# SenseBox-Eye_v1_2.net
KiCad netlist of a schematic drawn in EAGLE
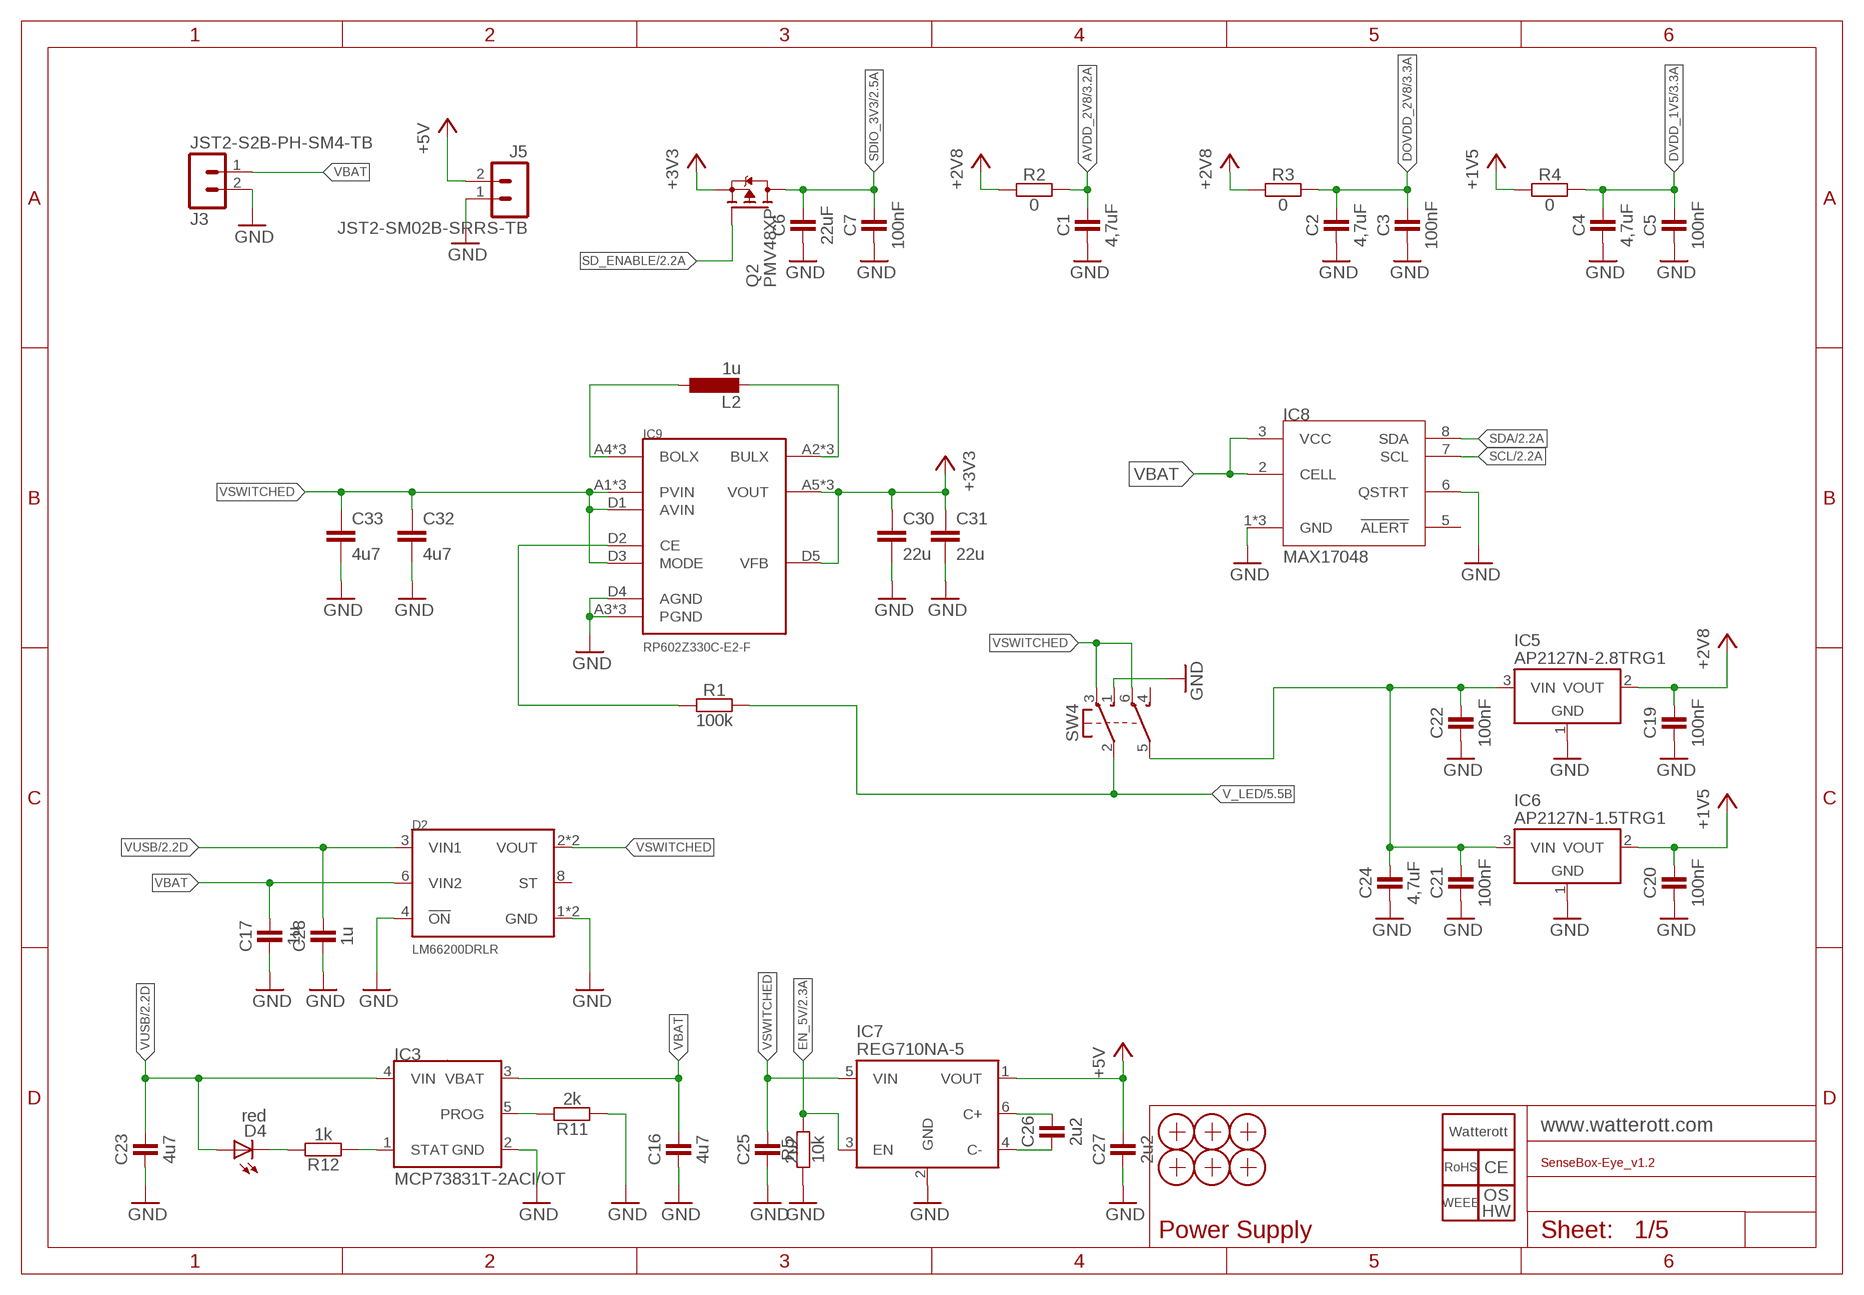
[diagram p0: schematic, sheet 1]
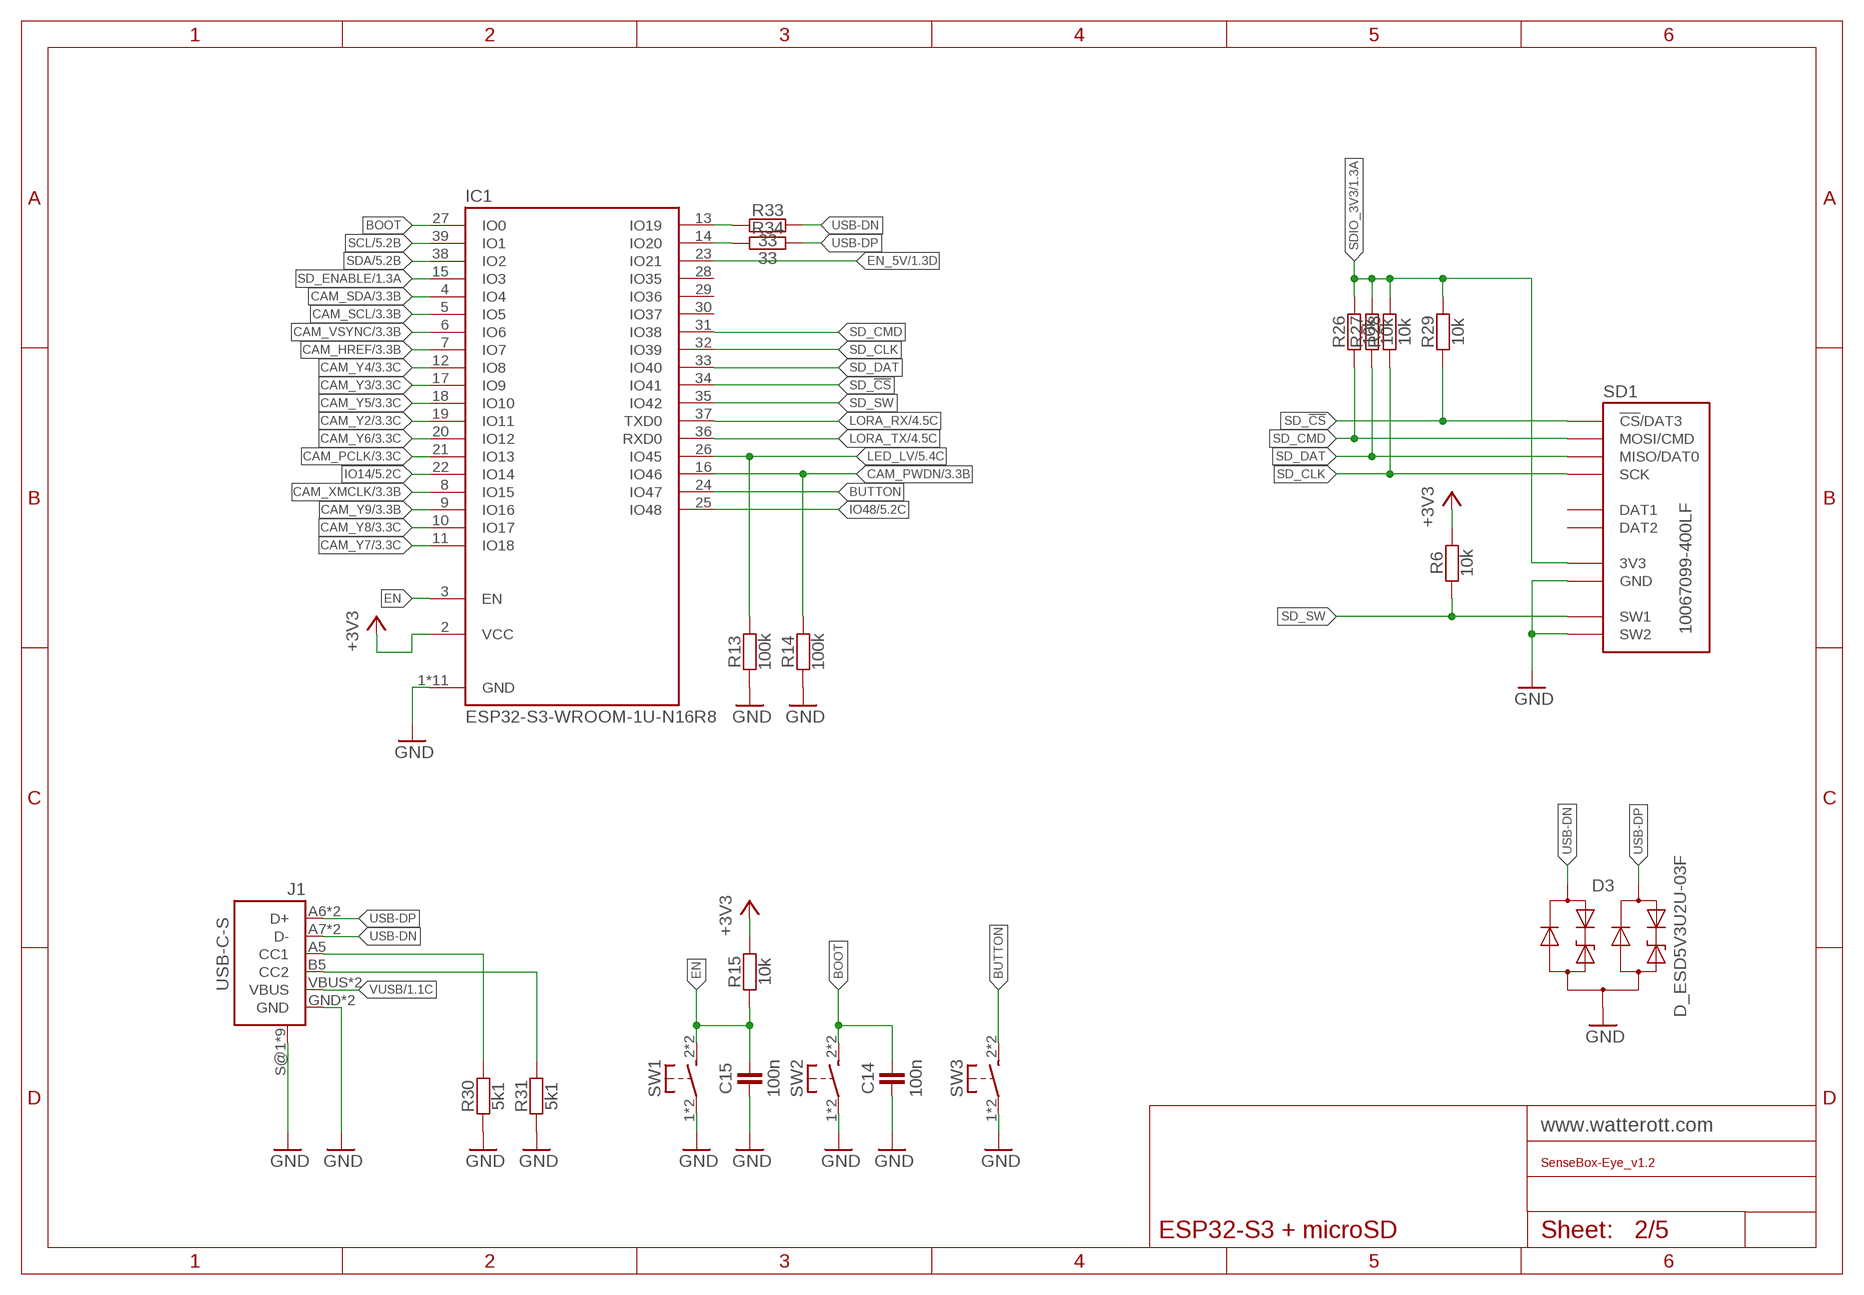
[diagram p1: schematic, sheet 2]
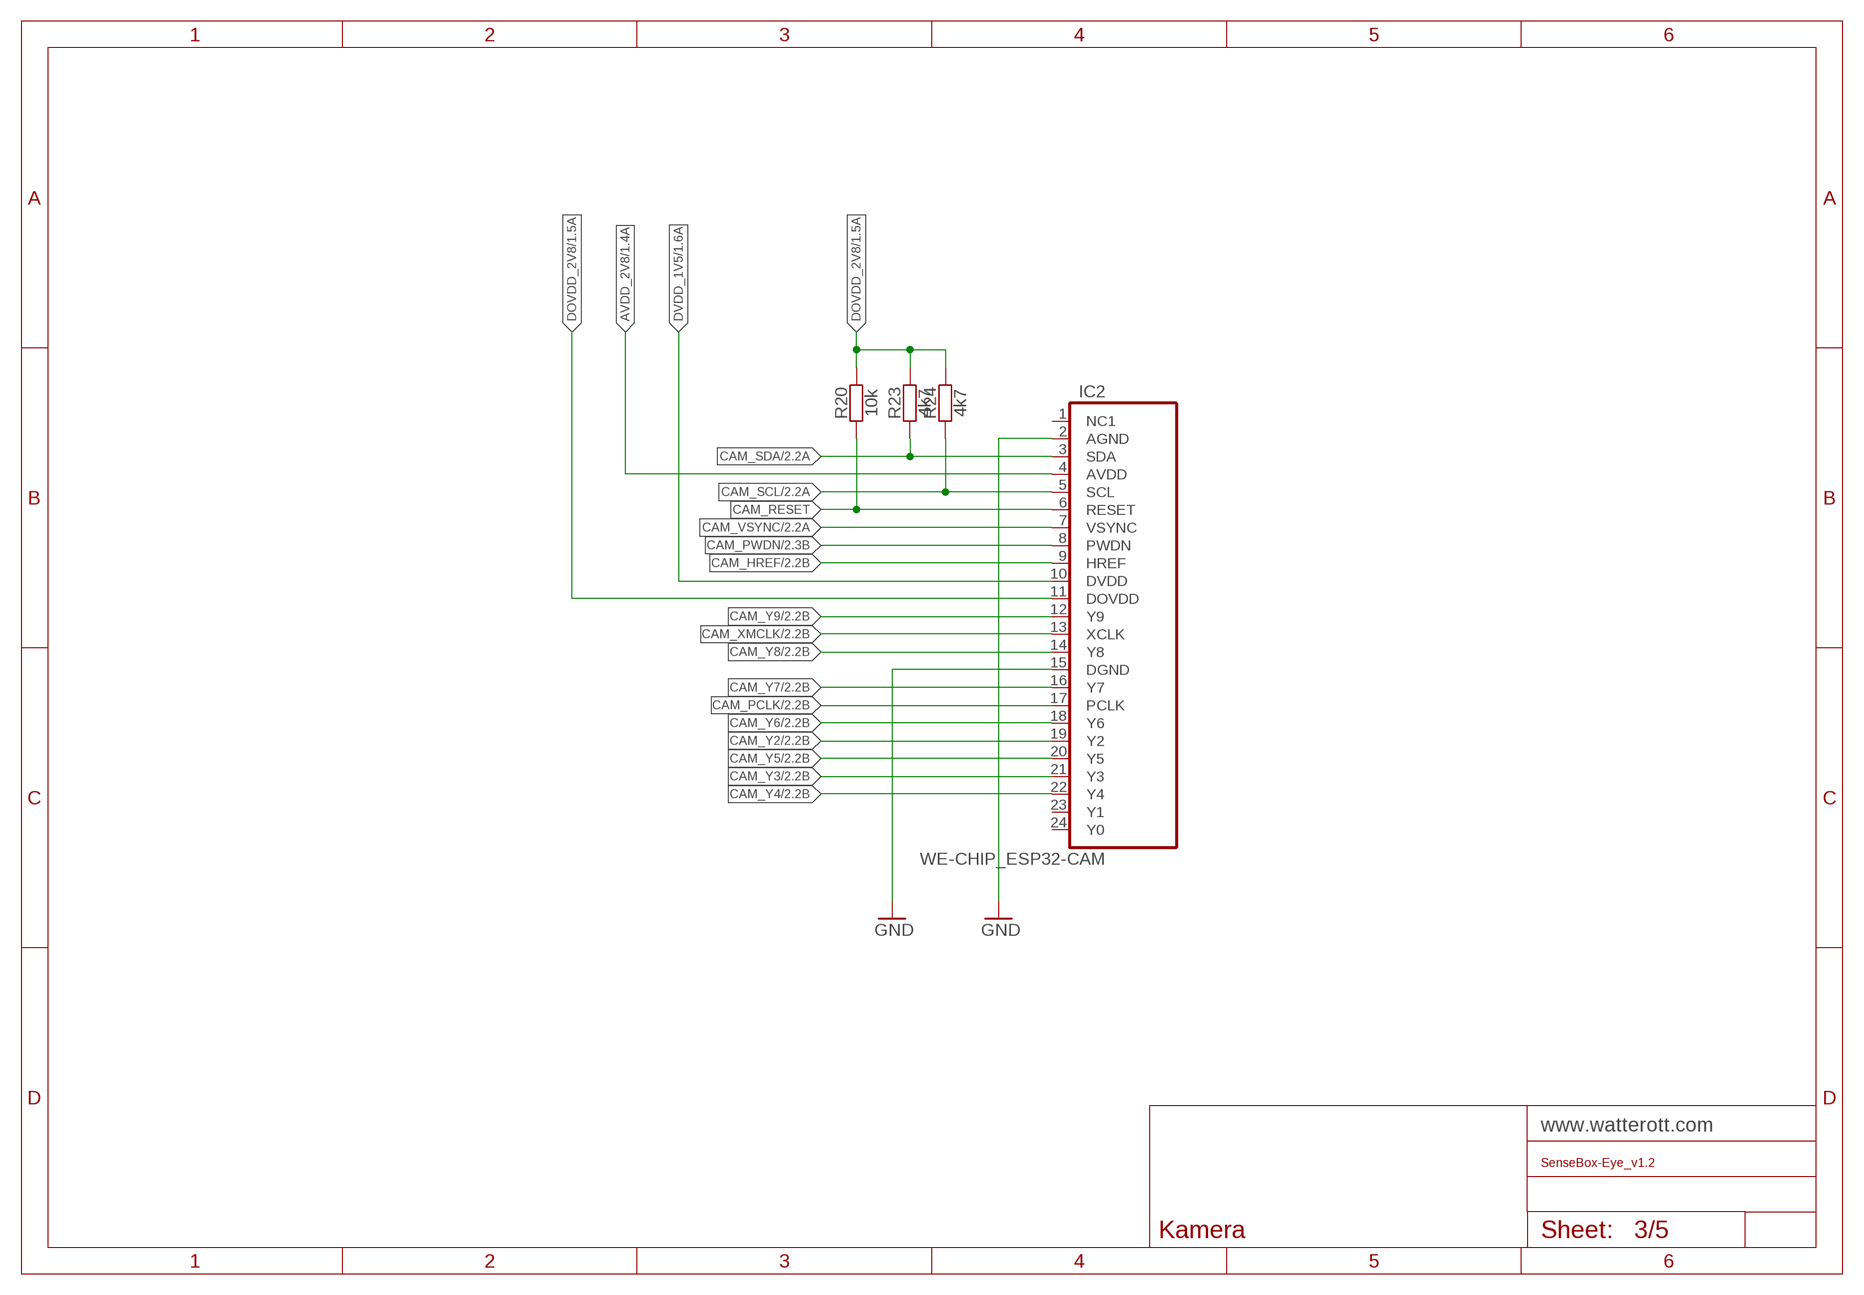
[diagram p2: schematic, sheet 3]
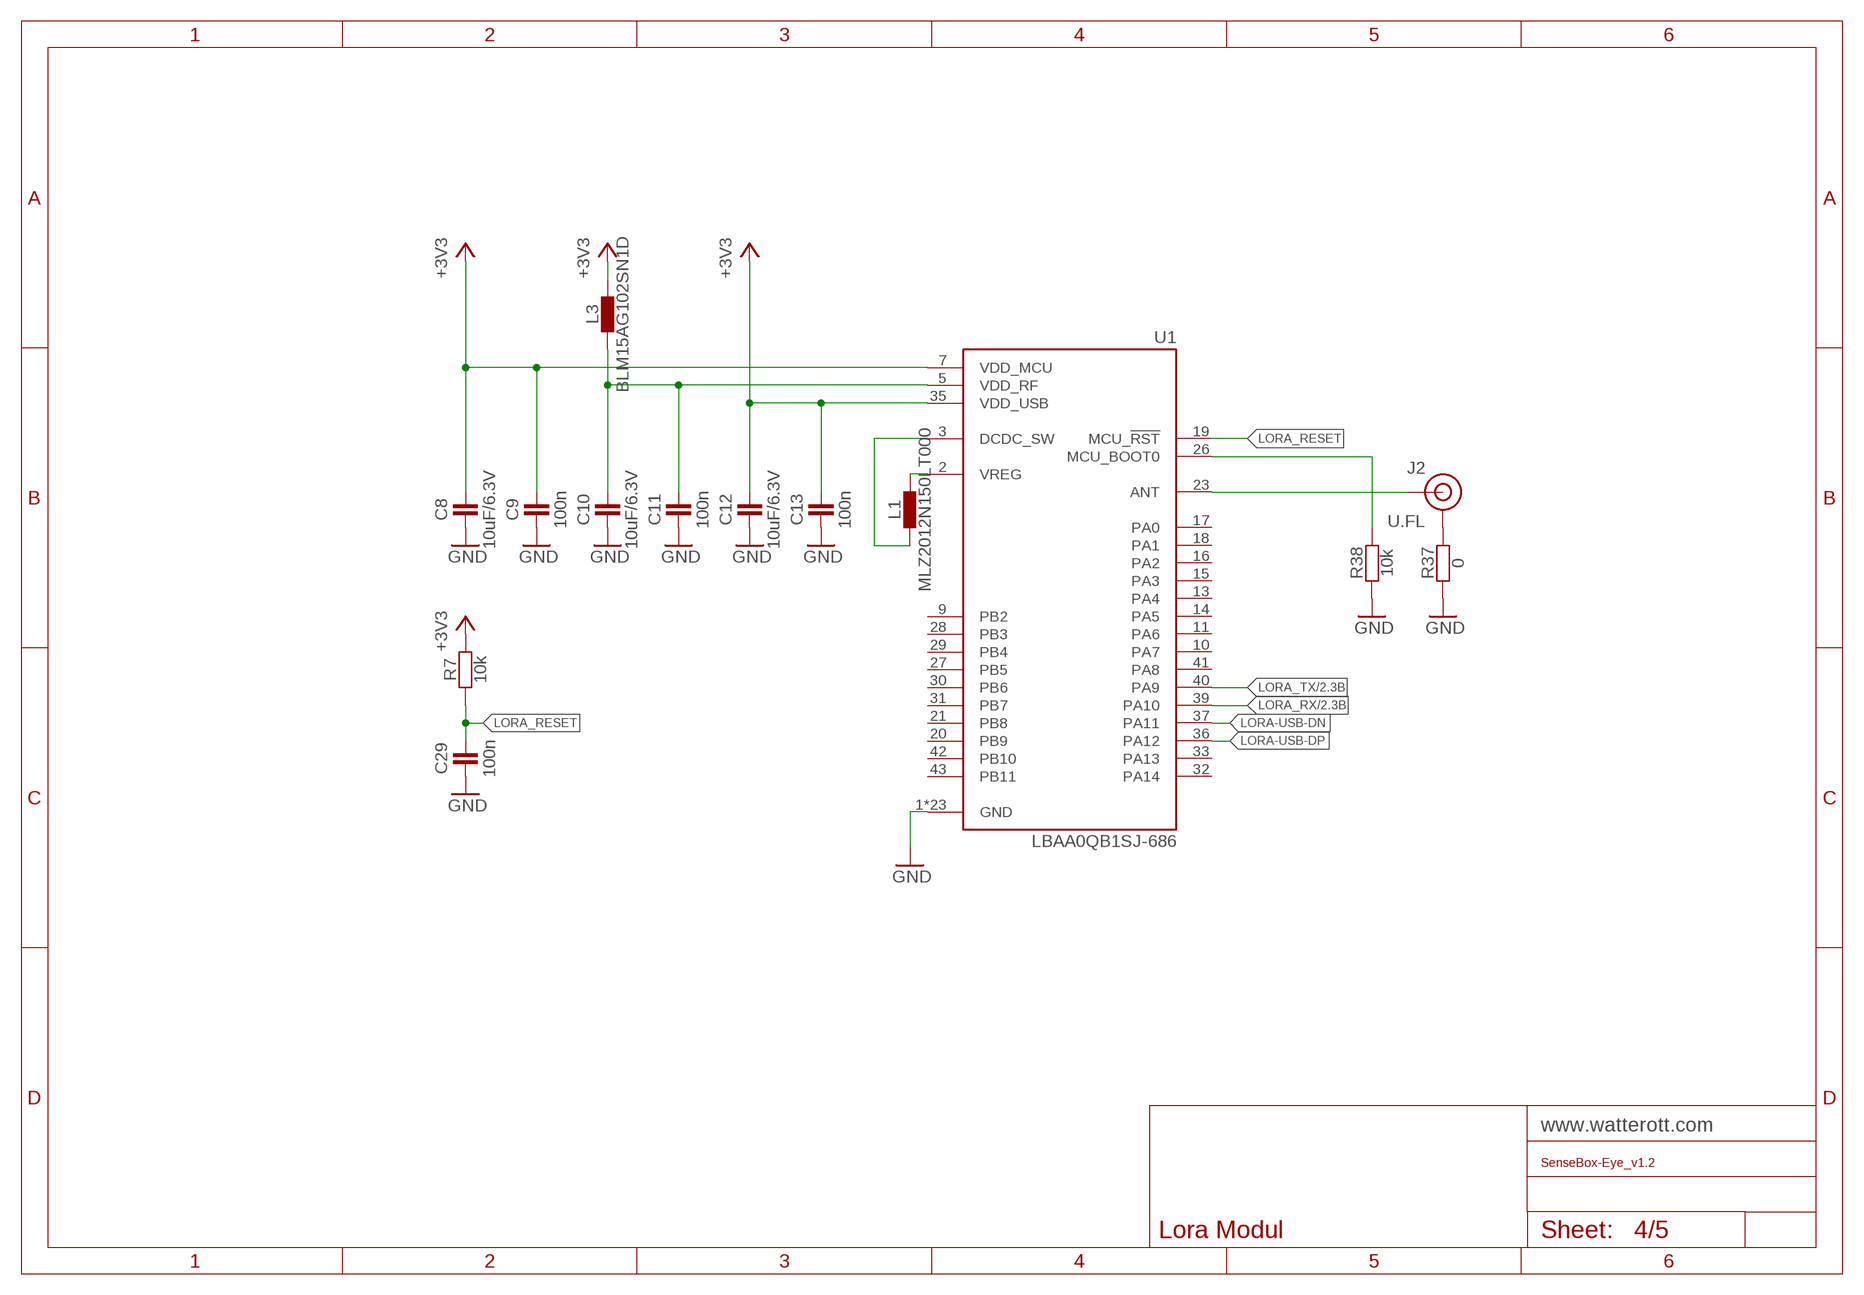
[diagram p3: schematic, sheet 4]
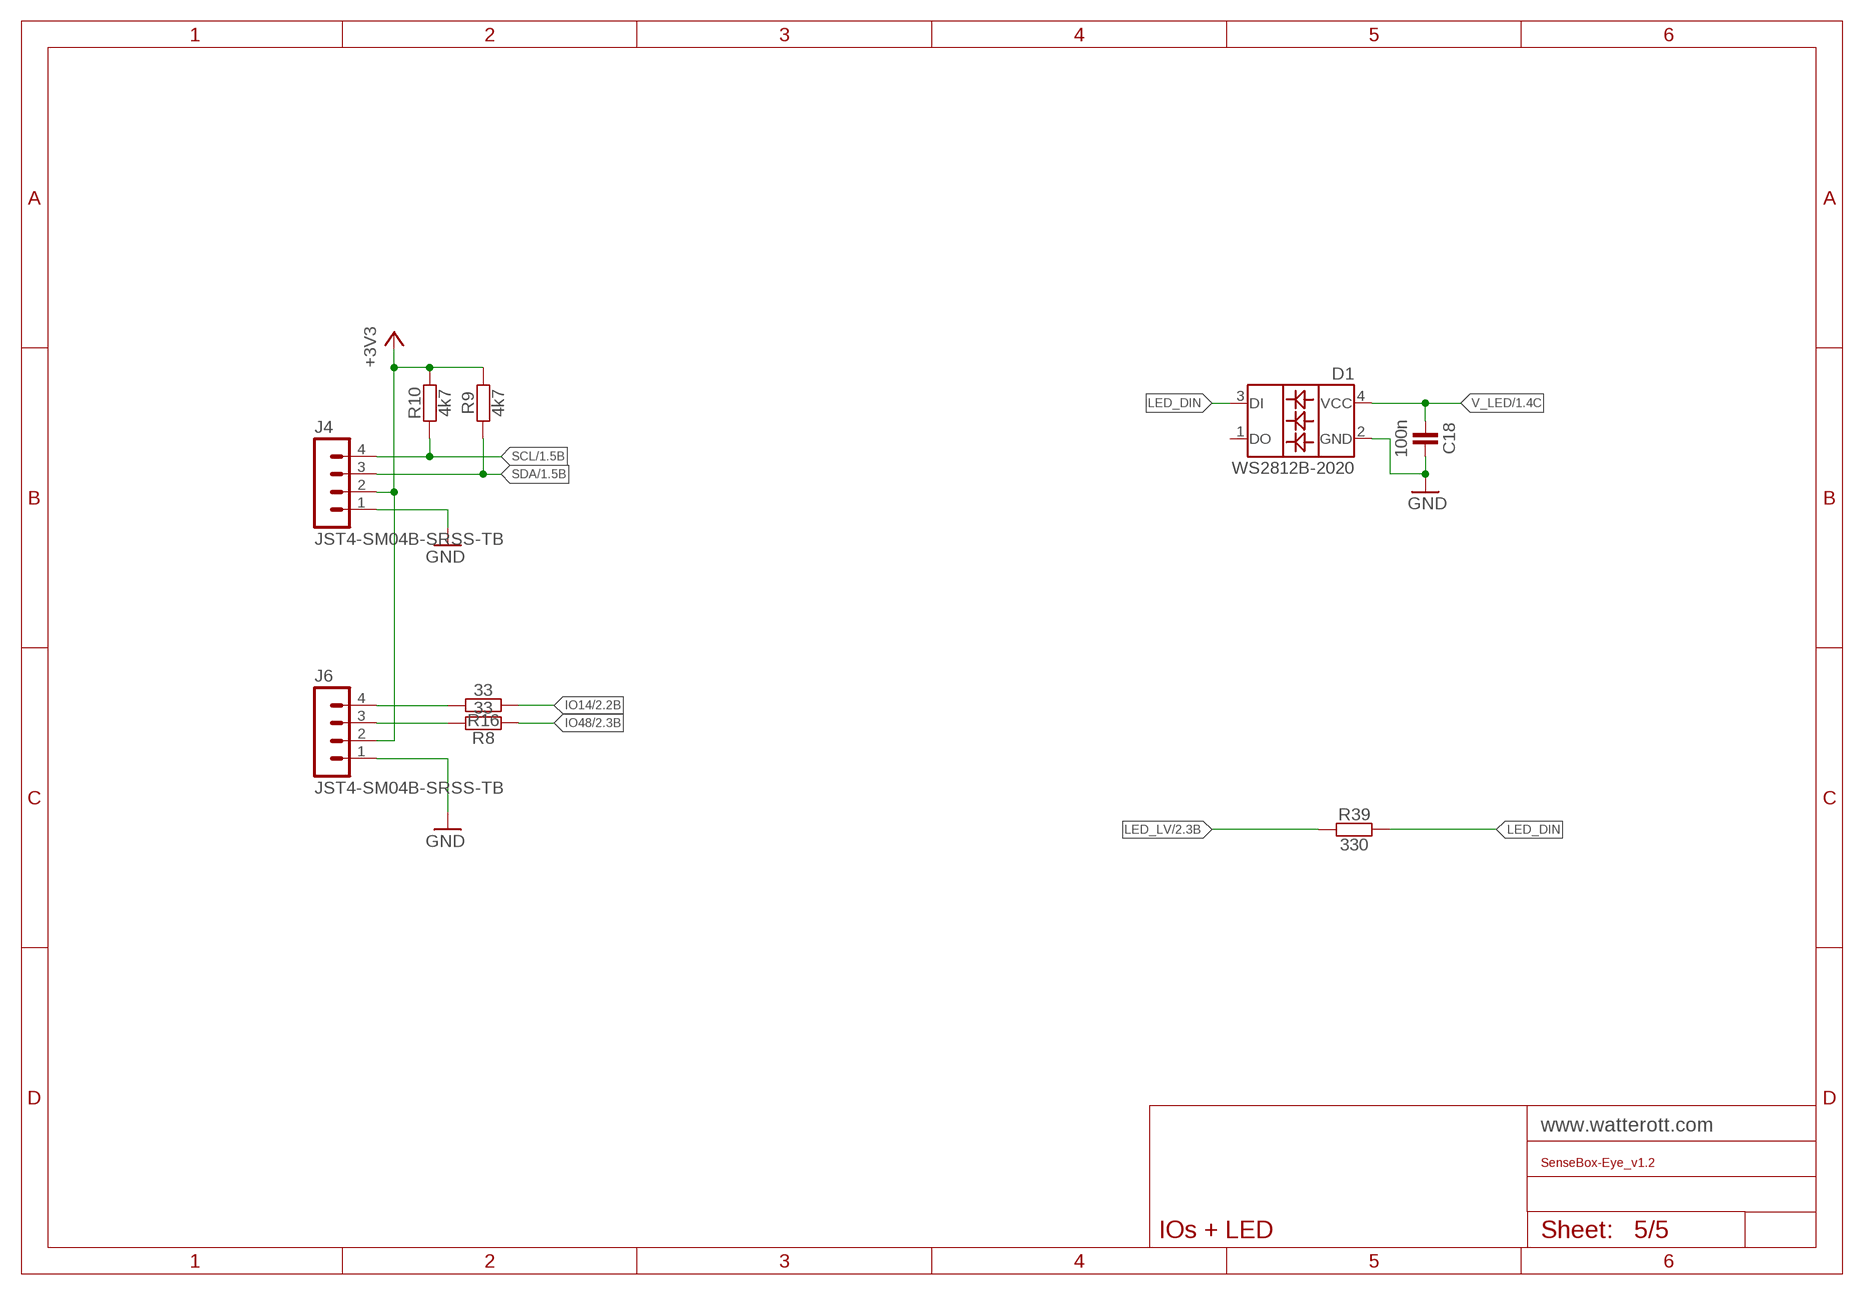
[diagram p4: schematic, sheet 5]

(export (version "E")
  (design (tool "Eeschema 10.0.6"))
  (components
    (comp (ref "C14")
      (value "100n")
      (footprint "eagle-import:C0402")
      (libsource (lib "eagle-import") (part "CAPACITOR-0402"))
    )
    (comp (ref "C15")
      (value "100n")
      (footprint "eagle-import:C0402")
      (libsource (lib "eagle-import") (part "CAPACITOR-0402"))
    )
    (comp (ref "D3")
      (value "D_ESD5V3U2U-03F")
      (footprint "eagle-import:SOT723")
      (libsource (lib "eagle-import") (part "D_ESD5V3U2U-03F"))
    )
    (comp (ref "IC1")
      (value "ESP32-S3-WROOM-1U-N16R8")
      (footprint "eagle-import:ESP32-S3-WROOM-1U")
      (libsource (lib "eagle-import") (part "ESP32_S3-WROOM-1"))
    )
    (comp (ref "J1")
      (value "USB-C-S")
      (footprint "eagle-import:USB-C-S")
      (libsource (lib "eagle-import") (part "USB-C-S"))
    )
    (comp (ref "R6")
      (value "10k")
      (footprint "eagle-import:C0402")
      (libsource (lib "eagle-import") (part "RESISTOR-0402"))
    )
    (comp (ref "R13")
      (value "100k")
      (footprint "eagle-import:C0402")
      (libsource (lib "eagle-import") (part "RESISTOR-0402"))
    )
    (comp (ref "R14")
      (value "100k")
      (footprint "eagle-import:C0402")
      (libsource (lib "eagle-import") (part "RESISTOR-0402"))
    )
    (comp (ref "R15")
      (value "10k")
      (footprint "eagle-import:C0402")
      (libsource (lib "eagle-import") (part "RESISTOR-0402"))
    )
    (comp (ref "R26")
      (value "10k")
      (footprint "eagle-import:C0402")
      (libsource (lib "eagle-import") (part "RESISTOR-0402"))
    )
    (comp (ref "R27")
      (value "10k")
      (footprint "eagle-import:C0402")
      (libsource (lib "eagle-import") (part "RESISTOR-0402"))
    )
    (comp (ref "R28")
      (value "10k")
      (footprint "eagle-import:C0402")
      (libsource (lib "eagle-import") (part "RESISTOR-0402"))
    )
    (comp (ref "R29")
      (value "10k")
      (footprint "eagle-import:C0402")
      (libsource (lib "eagle-import") (part "RESISTOR-0402"))
    )
    (comp (ref "R30")
      (value "5k1")
      (footprint "eagle-import:C0402")
      (libsource (lib "eagle-import") (part "RESISTOR-0402"))
    )
    (comp (ref "R31")
      (value "5k1")
      (footprint "eagle-import:C0402")
      (libsource (lib "eagle-import") (part "RESISTOR-0402"))
    )
    (comp (ref "R33")
      (value "33")
      (footprint "eagle-import:C0402")
      (libsource (lib "eagle-import") (part "RESISTOR-0402"))
    )
    (comp (ref "R34")
      (value "33")
      (footprint "eagle-import:C0402")
      (libsource (lib "eagle-import") (part "RESISTOR-0402"))
    )
    (comp (ref "SD1")
      (value "10067099-400LF")
      (footprint "eagle-import:SD_47309XXXX")
      (libsource (lib "eagle-import") (part "SD-CARD-MSD47"))
    )
    (comp (ref "SW1")
      (value "SW-TACTILE-TL3305")
      (footprint "eagle-import:TL3305")
      (libsource (lib "eagle-import") (part "SW-TACTILE-TL3305"))
    )
    (comp (ref "SW2")
      (value "SW-TACTILE-TL3305")
      (footprint "eagle-import:TL3305")
      (libsource (lib "eagle-import") (part "SW-TACTILE-TL3305"))
    )
    (comp (ref "SW3")
      (value "SW-TACTILE-TL3305")
      (footprint "eagle-import:TL3305")
      (libsource (lib "eagle-import") (part "SW-TACTILE-TL3305"))
    )
    (comp (ref "C8")
      (value "10uF/6.3V")
      (footprint "eagle-import:C0402")
      (libsource (lib "eagle-import") (part "CAPACITOR-0402"))
    )
    (comp (ref "C9")
      (value "100n")
      (footprint "eagle-import:C0402")
      (libsource (lib "eagle-import") (part "CAPACITOR-0402"))
    )
    (comp (ref "C10")
      (value "10uF/6.3V")
      (footprint "eagle-import:C0402")
      (libsource (lib "eagle-import") (part "CAPACITOR-0402"))
    )
    (comp (ref "C11")
      (value "100n")
      (footprint "eagle-import:C0402")
      (libsource (lib "eagle-import") (part "CAPACITOR-0402"))
    )
    (comp (ref "C12")
      (value "10uF/6.3V")
      (footprint "eagle-import:C0402")
      (libsource (lib "eagle-import") (part "CAPACITOR-0402"))
    )
    (comp (ref "C13")
      (value "100n")
      (footprint "eagle-import:C0402")
      (libsource (lib "eagle-import") (part "CAPACITOR-0402"))
    )
    (comp (ref "C29")
      (value "100n")
      (footprint "eagle-import:C0402")
      (libsource (lib "eagle-import") (part "CAPACITOR-0402"))
    )
    (comp (ref "J2")
      (value "U.FL")
      (footprint "eagle-import:U.FL")
      (libsource (lib "eagle-import") (part "U.FL"))
    )
    (comp (ref "L1")
      (value "MLZ2012N150LT000")
      (footprint "eagle-import:C0805")
      (libsource (lib "eagle-import") (part "INDUCTOR-0805"))
    )
    (comp (ref "L3")
      (value "BLM15AG102SN1D")
      (footprint "eagle-import:C0402")
      (libsource (lib "eagle-import") (part "INDUCTOR-0402"))
    )
    (comp (ref "R7")
      (value "10k")
      (footprint "eagle-import:C0402")
      (libsource (lib "eagle-import") (part "RESISTOR-0402"))
    )
    (comp (ref "R37")
      (value "0")
      (footprint "eagle-import:C0402")
      (libsource (lib "eagle-import") (part "RESISTOR-0402"))
    )
    (comp (ref "R38")
      (value "10k")
      (footprint "eagle-import:C0402")
      (libsource (lib "eagle-import") (part "RESISTOR-0402"))
    )
    (comp (ref "U1")
      (value "LBAA0QB1SJ-686")
      (footprint "eagle-import:MODULE_LBAA0QB1SJ-296")
      (fields (field (name "MANUFACTURER") "Murata"))
      (libsource (lib "eagle-import") (part "LBAA0QB1SJ-296"))
    )
    (comp (ref "IC2")
      (value "WE-CHIP_ESP32-CAM")
      (footprint "eagle-import:WE-CHIP_FPC24-0.5-CAM")
      (libsource (lib "eagle-import") (part "WE-CHIP_ESP32-CAM"))
    )
    (comp (ref "R20")
      (value "10k")
      (footprint "eagle-import:C0402")
      (libsource (lib "eagle-import") (part "RESISTOR-0402"))
    )
    (comp (ref "R23")
      (value "4k7")
      (footprint "eagle-import:C0402")
      (libsource (lib "eagle-import") (part "RESISTOR-0402"))
    )
    (comp (ref "R24")
      (value "4k7")
      (footprint "eagle-import:C0402")
      (libsource (lib "eagle-import") (part "RESISTOR-0402"))
    )
    (comp (ref "C18")
      (value "100n")
      (footprint "eagle-import:C0402")
      (libsource (lib "eagle-import") (part "CAPACITOR-0402"))
    )
    (comp (ref "D1")
      (value "WS2812B-2020")
      (footprint "eagle-import:WS2812_2020")
      (libsource (lib "eagle-import") (part "WS2812B-2020"))
    )
    (comp (ref "J4")
      (value "JST4-SM04B-SRSS-TB")
      (footprint "eagle-import:JST_SM04B-SRSS-TB")
      (libsource (lib "eagle-import") (part "JST4-SM04B-SRSS-TB"))
    )
    (comp (ref "J6")
      (value "JST4-SM04B-SRSS-TB")
      (footprint "eagle-import:JST_SM04B-SRSS-TB")
      (libsource (lib "eagle-import") (part "JST4-SM04B-SRSS-TB"))
    )
    (comp (ref "R8")
      (value "33")
      (footprint "eagle-import:C0402")
      (libsource (lib "eagle-import") (part "RESISTOR-0402"))
    )
    (comp (ref "R9")
      (value "4k7")
      (footprint "eagle-import:C0402")
      (libsource (lib "eagle-import") (part "RESISTOR-0402"))
    )
    (comp (ref "R10")
      (value "4k7")
      (footprint "eagle-import:C0402")
      (libsource (lib "eagle-import") (part "RESISTOR-0402"))
    )
    (comp (ref "R16")
      (value "33")
      (footprint "eagle-import:C0402")
      (libsource (lib "eagle-import") (part "RESISTOR-0402"))
    )
    (comp (ref "R39")
      (value "330")
      (footprint "eagle-import:C0402")
      (libsource (lib "eagle-import") (part "RESISTOR-0402"))
    )
    (comp (ref "C1")
      (value "4,7uF")
      (footprint "eagle-import:C0402")
      (libsource (lib "eagle-import") (part "CAPACITOR-0402"))
    )
    (comp (ref "C2")
      (value "4,7uF")
      (footprint "eagle-import:C0402")
      (libsource (lib "eagle-import") (part "CAPACITOR-0402"))
    )
    (comp (ref "C3")
      (value "100nF")
      (footprint "eagle-import:C0402")
      (libsource (lib "eagle-import") (part "CAPACITOR-0402"))
    )
    (comp (ref "C4")
      (value "4,7uF")
      (footprint "eagle-import:C0402")
      (libsource (lib "eagle-import") (part "CAPACITOR-0402"))
    )
    (comp (ref "C5")
      (value "100nF")
      (footprint "eagle-import:C0402")
      (libsource (lib "eagle-import") (part "CAPACITOR-0402"))
    )
    (comp (ref "C6")
      (value "22uF")
      (footprint "eagle-import:C0402")
      (libsource (lib "eagle-import") (part "CAPACITOR-0402"))
    )
    (comp (ref "C7")
      (value "100nF")
      (footprint "eagle-import:C0402")
      (libsource (lib "eagle-import") (part "CAPACITOR-0402"))
    )
    (comp (ref "C16")
      (value "4u7")
      (footprint "eagle-import:C0402")
      (libsource (lib "eagle-import") (part "CAPACITOR-0402"))
    )
    (comp (ref "C17")
      (value "1u")
      (footprint "eagle-import:C0402")
      (libsource (lib "eagle-import") (part "CAPACITOR-0402"))
    )
    (comp (ref "C19")
      (value "100nF")
      (footprint "eagle-import:C0402")
      (libsource (lib "eagle-import") (part "CAPACITOR-0402"))
    )
    (comp (ref "C20")
      (value "100nF")
      (footprint "eagle-import:C0402")
      (libsource (lib "eagle-import") (part "CAPACITOR-0402"))
    )
    (comp (ref "C21")
      (value "100nF")
      (footprint "eagle-import:C0402")
      (libsource (lib "eagle-import") (part "CAPACITOR-0402"))
    )
    (comp (ref "C22")
      (value "100nF")
      (footprint "eagle-import:C0402")
      (libsource (lib "eagle-import") (part "CAPACITOR-0402"))
    )
    (comp (ref "C23")
      (value "4u7")
      (footprint "eagle-import:C0402")
      (libsource (lib "eagle-import") (part "CAPACITOR-0402"))
    )
    (comp (ref "C24")
      (value "4,7uF")
      (footprint "eagle-import:C0402")
      (libsource (lib "eagle-import") (part "CAPACITOR-0402"))
    )
    (comp (ref "C25")
      (value "2u2")
      (footprint "eagle-import:C0402")
      (libsource (lib "eagle-import") (part "CAPACITOR-0402"))
    )
    (comp (ref "C26")
      (value "2u2")
      (footprint "eagle-import:C0402")
      (libsource (lib "eagle-import") (part "CAPACITOR-0402"))
    )
    (comp (ref "C27")
      (value "2u2")
      (footprint "eagle-import:C0402")
      (libsource (lib "eagle-import") (part "CAPACITOR-0402"))
    )
    (comp (ref "C28")
      (value "1u")
      (footprint "eagle-import:C0402")
      (libsource (lib "eagle-import") (part "CAPACITOR-0402"))
    )
    (comp (ref "C30")
      (value "22u")
      (footprint "eagle-import:0805N")
      (fields (field (name "VOLTAGE") "6V3"))
      (libsource (lib "eagle-import") (part "C_0805N_22U"))
    )
    (comp (ref "C31")
      (value "22u")
      (footprint "eagle-import:0805N")
      (fields (field (name "VOLTAGE") "6V3"))
      (libsource (lib "eagle-import") (part "C_0805N_22U"))
    )
    (comp (ref "C32")
      (value "4u7")
      (footprint "eagle-import:0603N")
      (fields (field (name "VOLTAGE") "6V3"))
      (libsource (lib "eagle-import") (part "C_0603N_4U7"))
    )
    (comp (ref "C33")
      (value "4u7")
      (footprint "eagle-import:0603N")
      (fields (field (name "VOLTAGE") "6V3"))
      (libsource (lib "eagle-import") (part "C_0603N_4U7"))
    )
    (comp (ref "D2")
      (value "LM66200DRLR")
      (footprint "eagle-import:SOT-5X3")
      (libsource (lib "eagle-import") (part "LM66200"))
    )
    (comp (ref "D4")
      (value "red")
      (footprint "eagle-import:0603N")
      (libsource (lib "eagle-import") (part "LED_0603N_RED"))
    )
    (comp (ref "IC3")
      (value "MCP73831T-2ACI/OT")
      (footprint "eagle-import:SOT23-5")
      (libsource (lib "eagle-import") (part "MCP73831_SOT23-5_MCP73831T-2ACI/OT"))
    )
    (comp (ref "IC5")
      (value "AP2127N-2.8TRG1")
      (footprint "eagle-import:SOT23")
      (libsource (lib "eagle-import") (part "VREG-TS9011-3V3"))
    )
    (comp (ref "IC6")
      (value "AP2127N-1.5TRG1")
      (footprint "eagle-import:SOT23")
      (libsource (lib "eagle-import") (part "VREG-TS9011-3V3"))
    )
    (comp (ref "IC7")
      (value "REG710NA-5")
      (footprint "eagle-import:SOT23-6")
      (libsource (lib "eagle-import") (part "REG710NA-5"))
    )
    (comp (ref "IC8")
      (value "MAX17048")
      (footprint "eagle-import:UDFN8_2020")
      (libsource (lib "eagle-import") (part "MAX1704X"))
    )
    (comp (ref "IC9")
      (value "RP602Z330C-E2-F")
      (footprint "eagle-import:WLCSP-20-P1")
      (libsource (lib "eagle-import") (part "RP602_WLCSP-20-P1_RP602Z330C-E2-F"))
    )
    (comp (ref "J3")
      (value "JST2-S2B-PH-SM4-TB")
      (footprint "eagle-import:JST_S2B-PH-SM4-TB")
      (libsource (lib "eagle-import") (part "JST2-S2B-PH-SM4-TB"))
    )
    (comp (ref "J5")
      (value "JST2-SM02B-SRRS-TB")
      (footprint "eagle-import:JST_SM02B-SRSS-TB")
      (libsource (lib "eagle-import") (part "JST2-SM02B-SRRS-TB"))
    )
    (comp (ref "L2")
      (value "1u")
      (footprint "eagle-import:5040")
      (libsource (lib "eagle-import") (part "L_5040_WE-LQS-1U"))
    )
    (comp (ref "LOGO2")
      (value "LOGO_CE-2")
      (footprint "eagle-import:CE_2MM")
      (libsource (lib "eagle-import") (part "LOGO_CE-2"))
    )
    (comp (ref "LOGO3")
      (value "LOGO_OSHW-2")
      (footprint "eagle-import:OSHW_2MM")
      (libsource (lib "eagle-import") (part "LOGO_OSHW-2"))
    )
    (comp (ref "LOGO4")
      (value "LOGO_ROHS-2")
      (footprint "eagle-import:ROHS_2MM")
      (libsource (lib "eagle-import") (part "LOGO_ROHS-2"))
    )
    (comp (ref "LOGO5")
      (value "LOGO_WEEE-4")
      (footprint "eagle-import:WEEE_4MM")
      (libsource (lib "eagle-import") (part "LOGO_WEEE-4"))
    )
    (comp (ref "LOGO6")
      (value "LOGO_SPARK-2")
      (footprint "eagle-import:SPARK_2MM")
      (libsource (lib "eagle-import") (part "LOGO_SPARK-2"))
    )
    (comp (ref "Q2")
      (value "PMV48XP")
      (footprint "eagle-import:SOT23")
      (fields (field (name "VOLTAGE") "20"))
      (libsource (lib "eagle-import") (part "MOSFET-P_SOT23'_PMV48XP"))
    )
    (comp (ref "R1")
      (value "100k")
      (footprint "eagle-import:C0402")
      (libsource (lib "eagle-import") (part "RESISTOR-0402"))
    )
    (comp (ref "R2")
      (value "0")
      (footprint "eagle-import:C0402")
      (libsource (lib "eagle-import") (part "RESISTOR-0402"))
    )
    (comp (ref "R3")
      (value "0")
      (footprint "eagle-import:C0402")
      (libsource (lib "eagle-import") (part "RESISTOR-0402"))
    )
    (comp (ref "R4")
      (value "0")
      (footprint "eagle-import:C0402")
      (libsource (lib "eagle-import") (part "RESISTOR-0402"))
    )
    (comp (ref "R5")
      (value "10k")
      (footprint "eagle-import:C0402")
      (libsource (lib "eagle-import") (part "RESISTOR-0402"))
    )
    (comp (ref "R11")
      (value "2k")
      (footprint "eagle-import:C0402")
      (libsource (lib "eagle-import") (part "RESISTOR-0402"))
    )
    (comp (ref "R12")
      (value "1k")
      (footprint "eagle-import:C0402")
      (libsource (lib "eagle-import") (part "RESISTOR-0402"))
    )
    (comp (ref "SW4")
      (value "SW-2UM-CUS22B")
      (footprint "eagle-import:CUS22B")
      (libsource (lib "eagle-import") (part "SW-2UM-CUS22B"))
    )
    (comp (ref "X1")
      (value "PASSER-04")
      (footprint "eagle-import:PASSER_04MM")
      (libsource (lib "eagle-import") (part "PASSER-04"))
    )
    (comp (ref "X2")
      (value "PASSER-04")
      (footprint "eagle-import:PASSER_04MM")
      (libsource (lib "eagle-import") (part "PASSER-04"))
    )
    (comp (ref "X3")
      (value "PASSER-04")
      (footprint "eagle-import:PASSER_04MM")
      (libsource (lib "eagle-import") (part "PASSER-04"))
    )
    (comp (ref "X4")
      (value "PASSER-04")
      (footprint "eagle-import:PASSER_04MM")
      (libsource (lib "eagle-import") (part "PASSER-04"))
    )
    (comp (ref "X5")
      (value "PASSER-04")
      (footprint "eagle-import:PASSER_04MM")
      (libsource (lib "eagle-import") (part "PASSER-04"))
    )
    (comp (ref "X6")
      (value "PASSER-04")
      (footprint "eagle-import:PASSER_04MM")
      (libsource (lib "eagle-import") (part "PASSER-04"))
    )
  )
  (nets
    (net (code "1") (name "+1V5") (class "Default")
      (node (ref "C20") (pin "2") (pinfunction "2_2") (pintype "passive"))
      (node (ref "IC6") (pin "2") (pinfunction "VOUT_2") (pintype "power_in"))
      (node (ref "R4") (pin "1") (pinfunction "1_1") (pintype "passive"))
    )
    (net (code "2") (name "+2V8") (class "Default")
      (node (ref "C19") (pin "2") (pinfunction "2_2") (pintype "passive"))
      (node (ref "IC5") (pin "2") (pinfunction "VOUT_2") (pintype "power_in"))
      (node (ref "R2") (pin "1") (pinfunction "1_1") (pintype "passive"))
      (node (ref "R3") (pin "1") (pinfunction "1_1") (pintype "passive"))
    )
    (net (code "3") (name "+3V3") (class "Default")
      (node (ref "C12") (pin "2") (pinfunction "2_2") (pintype "passive"))
      (node (ref "C13") (pin "2") (pinfunction "2_2") (pintype "passive"))
      (node (ref "C30") (pin "1") (pinfunction "1_1") (pintype "passive"))
      (node (ref "C31") (pin "1") (pinfunction "1_1") (pintype "passive"))
      (node (ref "C8") (pin "2") (pinfunction "2_2") (pintype "passive"))
      (node (ref "C9") (pin "2") (pinfunction "2_2") (pintype "passive"))
      (node (ref "IC1") (pin "2") (pinfunction "VCC_2") (pintype "power_in"))
      (node (ref "IC9") (pin "A5") (pinfunction "VOUT_A5") (pintype "power_in"))
      (node (ref "IC9") (pin "B5") (pinfunction "VOUT_B5") (pintype "power_in"))
      (node (ref "IC9") (pin "C5") (pinfunction "VOUT_C5") (pintype "power_in"))
      (node (ref "IC9") (pin "D5") (pinfunction "VFB_D5") (pintype "input"))
      (node (ref "J4") (pin "2") (pinfunction "2_2") (pintype "passive"))
      (node (ref "J6") (pin "2") (pinfunction "2_2") (pintype "passive"))
      (node (ref "L3") (pin "2") (pinfunction "2_2") (pintype "passive"))
      (node (ref "Q2") (pin "2") (pinfunction "S_2") (pintype "passive"))
      (node (ref "R10") (pin "1") (pinfunction "1_1") (pintype "passive"))
      (node (ref "R15") (pin "2") (pinfunction "2_2") (pintype "passive"))
      (node (ref "R6") (pin "2") (pinfunction "2_2") (pintype "passive"))
      (node (ref "R7") (pin "2") (pinfunction "2_2") (pintype "passive"))
      (node (ref "R9") (pin "1") (pinfunction "1_1") (pintype "passive"))
      (node (ref "U1") (pin "35") (pinfunction "VDD_USB_35") (pintype "power_in"))
      (node (ref "U1") (pin "7") (pinfunction "VDD_MCU_7") (pintype "power_in"))
    )
    (net (code "4") (name "+5V") (class "Default")
      (node (ref "C27") (pin "2") (pinfunction "2_2") (pintype "passive"))
      (node (ref "IC7") (pin "1") (pinfunction "VOUT_1") (pintype "power_in"))
      (node (ref "J5") (pin "2") (pinfunction "2_2") (pintype "passive"))
    )
    (net (code "5") (name "AVDD_2V8") (class "Default")
      (node (ref "C1") (pin "2") (pinfunction "2_2") (pintype "passive"))
      (node (ref "IC2") (pin "4") (pinfunction "AVDD_4") (pintype "bidirectional"))
      (node (ref "R2") (pin "2") (pinfunction "2_2") (pintype "passive"))
    )
    (net (code "6") (name "BOOT") (class "Default")
      (node (ref "C14") (pin "2") (pinfunction "2_2") (pintype "passive"))
      (node (ref "IC1") (pin "27") (pinfunction "IO0_27") (pintype "bidirectional"))
      (node (ref "SW2") (pin "2") (pinfunction "S1_2") (pintype "passive"))
      (node (ref "SW2") (pin "3") (pinfunction "S1_3") (pintype "passive"))
    )
    (net (code "7") (name "BUTTON") (class "Default")
      (node (ref "IC1") (pin "24") (pinfunction "IO47_24") (pintype "bidirectional"))
      (node (ref "SW3") (pin "2") (pinfunction "S1_2") (pintype "passive"))
      (node (ref "SW3") (pin "3") (pinfunction "S1_3") (pintype "passive"))
    )
    (net (code "8") (name "CAM_HREF") (class "Default")
      (node (ref "IC1") (pin "7") (pinfunction "IO7_7") (pintype "bidirectional"))
      (node (ref "IC2") (pin "9") (pinfunction "HREF_9") (pintype "bidirectional"))
    )
    (net (code "9") (name "CAM_PCLK") (class "Default")
      (node (ref "IC1") (pin "21") (pinfunction "IO13_21") (pintype "bidirectional"))
      (node (ref "IC2") (pin "17") (pinfunction "PCLK_17") (pintype "bidirectional"))
    )
    (net (code "10") (name "CAM_PWDN") (class "Default")
      (node (ref "IC1") (pin "16") (pinfunction "IO46_16") (pintype "bidirectional"))
      (node (ref "IC2") (pin "8") (pinfunction "PWDN_8") (pintype "bidirectional"))
      (node (ref "R14") (pin "2") (pinfunction "2_2") (pintype "passive"))
    )
    (net (code "11") (name "CAM_RESET") (class "Default")
      (node (ref "IC2") (pin "6") (pinfunction "RESET_6") (pintype "bidirectional"))
      (node (ref "R20") (pin "1") (pinfunction "1_1") (pintype "passive"))
    )
    (net (code "12") (name "CAM_SCL") (class "Default")
      (node (ref "IC1") (pin "5") (pinfunction "IO5_5") (pintype "bidirectional"))
      (node (ref "IC2") (pin "5") (pinfunction "SCL_5") (pintype "bidirectional"))
      (node (ref "R24") (pin "1") (pinfunction "1_1") (pintype "passive"))
    )
    (net (code "13") (name "CAM_SDA") (class "Default")
      (node (ref "IC1") (pin "4") (pinfunction "IO4_4") (pintype "bidirectional"))
      (node (ref "IC2") (pin "3") (pinfunction "SDA_3") (pintype "bidirectional"))
      (node (ref "R23") (pin "1") (pinfunction "1_1") (pintype "passive"))
    )
    (net (code "14") (name "CAM_VSYNC") (class "Default")
      (node (ref "IC1") (pin "6") (pinfunction "IO6_6") (pintype "bidirectional"))
      (node (ref "IC2") (pin "7") (pinfunction "VSYNC_7") (pintype "bidirectional"))
    )
    (net (code "15") (name "CAM_XMCLK") (class "Default")
      (node (ref "IC1") (pin "8") (pinfunction "IO15_8") (pintype "bidirectional"))
      (node (ref "IC2") (pin "13") (pinfunction "XCLK_13") (pintype "bidirectional"))
    )
    (net (code "16") (name "CAM_Y2") (class "Default")
      (node (ref "IC1") (pin "19") (pinfunction "IO11_19") (pintype "bidirectional"))
      (node (ref "IC2") (pin "19") (pinfunction "Y2_19") (pintype "bidirectional"))
    )
    (net (code "17") (name "CAM_Y3") (class "Default")
      (node (ref "IC1") (pin "17") (pinfunction "IO9_17") (pintype "bidirectional"))
      (node (ref "IC2") (pin "21") (pinfunction "Y3_21") (pintype "bidirectional"))
    )
    (net (code "18") (name "CAM_Y4") (class "Default")
      (node (ref "IC1") (pin "12") (pinfunction "IO8_12") (pintype "bidirectional"))
      (node (ref "IC2") (pin "22") (pinfunction "Y4_22") (pintype "bidirectional"))
    )
    (net (code "19") (name "CAM_Y5") (class "Default")
      (node (ref "IC1") (pin "18") (pinfunction "IO10_18") (pintype "bidirectional"))
      (node (ref "IC2") (pin "20") (pinfunction "Y5_20") (pintype "bidirectional"))
    )
    (net (code "20") (name "CAM_Y6") (class "Default")
      (node (ref "IC1") (pin "20") (pinfunction "IO12_20") (pintype "bidirectional"))
      (node (ref "IC2") (pin "18") (pinfunction "Y6_18") (pintype "bidirectional"))
    )
    (net (code "21") (name "CAM_Y7") (class "Default")
      (node (ref "IC1") (pin "11") (pinfunction "IO18_11") (pintype "bidirectional"))
      (node (ref "IC2") (pin "16") (pinfunction "Y7_16") (pintype "bidirectional"))
    )
    (net (code "22") (name "CAM_Y8") (class "Default")
      (node (ref "IC1") (pin "10") (pinfunction "IO17_10") (pintype "bidirectional"))
      (node (ref "IC2") (pin "14") (pinfunction "Y8_14") (pintype "bidirectional"))
    )
    (net (code "23") (name "CAM_Y9") (class "Default")
      (node (ref "IC1") (pin "9") (pinfunction "IO16_9") (pintype "bidirectional"))
      (node (ref "IC2") (pin "12") (pinfunction "Y9_12") (pintype "bidirectional"))
    )
    (net (code "24") (name "DOVDD_2V8") (class "Default")
      (node (ref "C2") (pin "2") (pinfunction "2_2") (pintype "passive"))
      (node (ref "C3") (pin "2") (pinfunction "2_2") (pintype "passive"))
      (node (ref "IC2") (pin "11") (pinfunction "DOVDD_11") (pintype "bidirectional"))
      (node (ref "R20") (pin "2") (pinfunction "2_2") (pintype "passive"))
      (node (ref "R23") (pin "2") (pinfunction "2_2") (pintype "passive"))
      (node (ref "R24") (pin "2") (pinfunction "2_2") (pintype "passive"))
      (node (ref "R3") (pin "2") (pinfunction "2_2") (pintype "passive"))
    )
    (net (code "25") (name "DVDD_1V5") (class "Default")
      (node (ref "C4") (pin "2") (pinfunction "2_2") (pintype "passive"))
      (node (ref "C5") (pin "2") (pinfunction "2_2") (pintype "passive"))
      (node (ref "IC2") (pin "10") (pinfunction "DVDD_10") (pintype "bidirectional"))
      (node (ref "R4") (pin "2") (pinfunction "2_2") (pintype "passive"))
    )
    (net (code "26") (name "EN") (class "Default")
      (node (ref "C15") (pin "2") (pinfunction "2_2") (pintype "passive"))
      (node (ref "IC1") (pin "3") (pinfunction "EN_3") (pintype "bidirectional"))
      (node (ref "R15") (pin "1") (pinfunction "1_1") (pintype "passive"))
      (node (ref "SW1") (pin "2") (pinfunction "S1_2") (pintype "passive"))
      (node (ref "SW1") (pin "3") (pinfunction "S1_3") (pintype "passive"))
    )
    (net (code "27") (name "EN_5V") (class "Default")
      (node (ref "IC1") (pin "23") (pinfunction "IO21_23") (pintype "bidirectional"))
      (node (ref "IC7") (pin "3") (pinfunction "EN_3") (pintype "passive"))
      (node (ref "R5") (pin "2") (pinfunction "2_2") (pintype "passive"))
    )
    (net (code "28") (name "GND") (class "Default")
      (node (ref "C1") (pin "1") (pinfunction "1_1") (pintype "passive"))
      (node (ref "C10") (pin "1") (pinfunction "1_1") (pintype "passive"))
      (node (ref "C11") (pin "1") (pinfunction "1_1") (pintype "passive"))
      (node (ref "C12") (pin "1") (pinfunction "1_1") (pintype "passive"))
      (node (ref "C13") (pin "1") (pinfunction "1_1") (pintype "passive"))
      (node (ref "C14") (pin "1") (pinfunction "1_1") (pintype "passive"))
      (node (ref "C15") (pin "1") (pinfunction "1_1") (pintype "passive"))
      (node (ref "C16") (pin "1") (pinfunction "1_1") (pintype "passive"))
      (node (ref "C17") (pin "1") (pinfunction "1_1") (pintype "passive"))
      (node (ref "C18") (pin "1") (pinfunction "1_1") (pintype "passive"))
      (node (ref "C19") (pin "1") (pinfunction "1_1") (pintype "passive"))
      (node (ref "C2") (pin "1") (pinfunction "1_1") (pintype "passive"))
      (node (ref "C20") (pin "1") (pinfunction "1_1") (pintype "passive"))
      (node (ref "C21") (pin "1") (pinfunction "1_1") (pintype "passive"))
      (node (ref "C22") (pin "1") (pinfunction "1_1") (pintype "passive"))
      (node (ref "C23") (pin "1") (pinfunction "1_1") (pintype "passive"))
      (node (ref "C24") (pin "1") (pinfunction "1_1") (pintype "passive"))
      (node (ref "C25") (pin "1") (pinfunction "1_1") (pintype "passive"))
      (node (ref "C27") (pin "1") (pinfunction "1_1") (pintype "passive"))
      (node (ref "C28") (pin "1") (pinfunction "1_1") (pintype "passive"))
      (node (ref "C29") (pin "1") (pinfunction "1_1") (pintype "passive"))
      (node (ref "C3") (pin "1") (pinfunction "1_1") (pintype "passive"))
      (node (ref "C30") (pin "2") (pinfunction "2_2") (pintype "passive"))
      (node (ref "C31") (pin "2") (pinfunction "2_2") (pintype "passive"))
      (node (ref "C32") (pin "2") (pinfunction "2_2") (pintype "passive"))
      (node (ref "C33") (pin "2") (pinfunction "2_2") (pintype "passive"))
      (node (ref "C4") (pin "1") (pinfunction "1_1") (pintype "passive"))
      (node (ref "C5") (pin "1") (pinfunction "1_1") (pintype "passive"))
      (node (ref "C6") (pin "1") (pinfunction "1_1") (pintype "passive"))
      (node (ref "C7") (pin "1") (pinfunction "1_1") (pintype "passive"))
      (node (ref "C8") (pin "1") (pinfunction "1_1") (pintype "passive"))
      (node (ref "C9") (pin "1") (pinfunction "1_1") (pintype "passive"))
      (node (ref "D1") (pin "2") (pinfunction "GND_2") (pintype "power_in"))
      (node (ref "D2") (pin "1") (pinfunction "GND_1") (pintype "power_in"))
      (node (ref "D2") (pin "4") (pinfunction "~{ON}_4") (pintype "input"))
      (node (ref "D2") (pin "5") (pinfunction "GND_5") (pintype "power_in"))
      (node (ref "D3") (pin "3") (pinfunction "A_3") (pintype "passive"))
      (node (ref "IC1") (pin "1") (pinfunction "GND_1") (pintype "power_in"))
      (node (ref "IC1") (pin "40") (pinfunction "GND_40") (pintype "power_in"))
      (node (ref "IC1") (pin "P$1") (pinfunction "GND_P$1") (pintype "power_in"))
      (node (ref "IC1") (pin "P$2") (pinfunction "GND_P$2") (pintype "power_in"))
      (node (ref "IC1") (pin "P$3") (pinfunction "GND_P$3") (pintype "power_in"))
      (node (ref "IC1") (pin "P$4") (pinfunction "GND_P$4") (pintype "power_in"))
      (node (ref "IC1") (pin "P$5") (pinfunction "GND_P$5") (pintype "power_in"))
      (node (ref "IC1") (pin "P$6") (pinfunction "GND_P$6") (pintype "power_in"))
      (node (ref "IC1") (pin "P$7") (pinfunction "GND_P$7") (pintype "power_in"))
      (node (ref "IC1") (pin "P$8") (pinfunction "GND_P$8") (pintype "power_in"))
      (node (ref "IC1") (pin "P$9") (pinfunction "GND_P$9") (pintype "power_in"))
      (node (ref "IC2") (pin "15") (pinfunction "DGND_15") (pintype "bidirectional"))
      (node (ref "IC2") (pin "2") (pinfunction "AGND_2") (pintype "bidirectional"))
      (node (ref "IC3") (pin "2") (pinfunction "GND_2") (pintype "power_in"))
      (node (ref "IC5") (pin "1") (pinfunction "GND_1") (pintype "power_in"))
      (node (ref "IC6") (pin "1") (pinfunction "GND_1") (pintype "power_in"))
      (node (ref "IC7") (pin "2") (pinfunction "GND_2") (pintype "power_in"))
      (node (ref "IC8") (pin "1") (pinfunction "GND_1") (pintype "bidirectional"))
      (node (ref "IC8") (pin "4") (pinfunction "GND_4") (pintype "bidirectional"))
      (node (ref "IC8") (pin "6") (pinfunction "QSTRT_6") (pintype "bidirectional"))
      (node (ref "IC8") (pin "TP") (pinfunction "GND_TP") (pintype "bidirectional"))
      (node (ref "IC9") (pin "A3") (pinfunction "PGND_A3") (pintype "power_in"))
      (node (ref "IC9") (pin "B3") (pinfunction "PGND_B3") (pintype "power_in"))
      (node (ref "IC9") (pin "C3") (pinfunction "PGND_C3") (pintype "power_in"))
      (node (ref "IC9") (pin "D4") (pinfunction "AGND_D4") (pintype "power_in"))
      (node (ref "J1") (pin "GND") (pinfunction "GND_GND") (pintype "power_in"))
      (node (ref "J1") (pin "GND2") (pinfunction "GND_GND2") (pintype "power_in"))
      (node (ref "J1") (pin "S@1") (pinfunction "SHIELD_S@1") (pintype "passive"))
      (node (ref "J1") (pin "S@2") (pinfunction "SHIELD_S@2") (pintype "passive"))
      (node (ref "J1") (pin "S@3") (pinfunction "SHIELD_S@3") (pintype "passive"))
      (node (ref "J1") (pin "S@4") (pinfunction "SHIELD_S@4") (pintype "passive"))
      (node (ref "J1") (pin "S@5") (pinfunction "SHIELD_S@5") (pintype "passive"))
      (node (ref "J1") (pin "S@6") (pinfunction "SHIELD_S@6") (pintype "passive"))
      (node (ref "J1") (pin "S@7") (pinfunction "SHIELD_S@7") (pintype "passive"))
      (node (ref "J1") (pin "S@8") (pinfunction "SHIELD_S@8") (pintype "passive"))
      (node (ref "J1") (pin "S@9") (pinfunction "SHIELD_S@9") (pintype "passive"))
      (node (ref "J3") (pin "2") (pinfunction "2_2") (pintype "passive"))
      (node (ref "J4") (pin "1") (pinfunction "1_1") (pintype "passive"))
      (node (ref "J5") (pin "1") (pinfunction "1_1") (pintype "passive"))
      (node (ref "J6") (pin "1") (pinfunction "1_1") (pintype "passive"))
      (node (ref "R11") (pin "1") (pinfunction "1_1") (pintype "passive"))
      (node (ref "R13") (pin "1") (pinfunction "1_1") (pintype "passive"))
      (node (ref "R14") (pin "1") (pinfunction "1_1") (pintype "passive"))
      (node (ref "R30") (pin "1") (pinfunction "1_1") (pintype "passive"))
      (node (ref "R31") (pin "1") (pinfunction "1_1") (pintype "passive"))
      (node (ref "R37") (pin "1") (pinfunction "1_1") (pintype "passive"))
      (node (ref "R38") (pin "1") (pinfunction "1_1") (pintype "passive"))
      (node (ref "R5") (pin "1") (pinfunction "1_1") (pintype "passive"))
      (node (ref "SD1") (pin "GND") (pinfunction "GND_GND") (pintype "bidirectional"))
      (node (ref "SD1") (pin "GND@1") (pinfunction "GND_GND@1") (pintype "bidirectional"))
      (node (ref "SD1") (pin "GND@2") (pinfunction "GND_GND@2") (pintype "bidirectional"))
      (node (ref "SD1") (pin "SW2") (pinfunction "SW2_SW2") (pintype "bidirectional"))
      (node (ref "SW1") (pin "1") (pinfunction "P1_1") (pintype "passive"))
      (node (ref "SW1") (pin "4") (pinfunction "P1_4") (pintype "passive"))
      (node (ref "SW2") (pin "1") (pinfunction "P1_1") (pintype "passive"))
      (node (ref "SW2") (pin "4") (pinfunction "P1_4") (pintype "passive"))
      (node (ref "SW3") (pin "1") (pinfunction "P1_1") (pintype "passive"))
      (node (ref "SW3") (pin "4") (pinfunction "P1_4") (pintype "passive"))
      (node (ref "SW4") (pin "1") (pinfunction "NO1_1") (pintype "passive"))
      (node (ref "U1") (pin "1") (pinfunction "GND_1") (pintype "power_in"))
      (node (ref "U1") (pin "12") (pinfunction "GND_12") (pintype "power_in"))
      (node (ref "U1") (pin "22") (pinfunction "GND_22") (pintype "power_in"))
      (node (ref "U1") (pin "24") (pinfunction "GND_24") (pintype "power_in"))
      (node (ref "U1") (pin "25") (pinfunction "GND_25") (pintype "power_in"))
      (node (ref "U1") (pin "34") (pinfunction "GND_34") (pintype "power_in"))
      (node (ref "U1") (pin "38") (pinfunction "GND_38") (pintype "power_in"))
      (node (ref "U1") (pin "4") (pinfunction "GND_4") (pintype "power_in"))
      (node (ref "U1") (pin "44") (pinfunction "GND_44") (pintype "power_in"))
      (node (ref "U1") (pin "45") (pinfunction "GND_45") (pintype "power_in"))
      (node (ref "U1") (pin "46") (pinfunction "GND_46") (pintype "power_in"))
      (node (ref "U1") (pin "47") (pinfunction "GND_47") (pintype "power_in"))
      (node (ref "U1") (pin "48") (pinfunction "GND_48") (pintype "power_in"))
      (node (ref "U1") (pin "49") (pinfunction "GND_49") (pintype "power_in"))
      (node (ref "U1") (pin "50") (pinfunction "GND_50") (pintype "power_in"))
      (node (ref "U1") (pin "51") (pinfunction "GND_51") (pintype "power_in"))
      (node (ref "U1") (pin "52") (pinfunction "GND_52") (pintype "power_in"))
      (node (ref "U1") (pin "53") (pinfunction "GND_53") (pintype "power_in"))
      (node (ref "U1") (pin "54") (pinfunction "GND_54") (pintype "power_in"))
      (node (ref "U1") (pin "55") (pinfunction "GND_55") (pintype "power_in"))
      (node (ref "U1") (pin "56") (pinfunction "GND_56") (pintype "power_in"))
      (node (ref "U1") (pin "6") (pinfunction "GND_6") (pintype "power_in"))
      (node (ref "U1") (pin "8") (pinfunction "GND_8") (pintype "power_in"))
    )
    (net (code "29") (name "IO14") (class "Default")
      (node (ref "IC1") (pin "22") (pinfunction "IO14_22") (pintype "bidirectional"))
      (node (ref "R16") (pin "2") (pinfunction "2_2") (pintype "passive"))
    )
    (net (code "30") (name "IO48") (class "Default")
      (node (ref "IC1") (pin "25") (pinfunction "IO48_25") (pintype "bidirectional"))
      (node (ref "R8") (pin "2") (pinfunction "2_2") (pintype "passive"))
    )
    (net (code "31") (name "LED_DIN") (class "Default")
      (node (ref "D1") (pin "3") (pinfunction "DI_3") (pintype "bidirectional"))
      (node (ref "R39") (pin "2") (pinfunction "2_2") (pintype "passive"))
    )
    (net (code "32") (name "LED_LV") (class "Default")
      (node (ref "IC1") (pin "26") (pinfunction "IO45_26") (pintype "bidirectional"))
      (node (ref "R13") (pin "2") (pinfunction "2_2") (pintype "passive"))
      (node (ref "R39") (pin "1") (pinfunction "1_1") (pintype "passive"))
    )
    (net (code "33") (name "LORA-USB-DN") (class "Default")
      (node (ref "U1") (pin "37") (pinfunction "PA11_37") (pintype "bidirectional"))
    )
    (net (code "34") (name "LORA-USB-DP") (class "Default")
      (node (ref "U1") (pin "36") (pinfunction "PA12_36") (pintype "bidirectional"))
    )
    (net (code "35") (name "LORA_RESET") (class "Default")
      (node (ref "C29") (pin "2") (pinfunction "2_2") (pintype "passive"))
      (node (ref "R7") (pin "1") (pinfunction "1_1") (pintype "passive"))
      (node (ref "U1") (pin "19") (pinfunction "MCU_~{RST}_19") (pintype "input"))
    )
    (net (code "36") (name "LORA_RX") (class "Default")
      (node (ref "IC1") (pin "37") (pinfunction "TXD0_37") (pintype "bidirectional"))
      (node (ref "U1") (pin "39") (pinfunction "PA10_39") (pintype "bidirectional"))
    )
    (net (code "37") (name "LORA_TX") (class "Default")
      (node (ref "IC1") (pin "36") (pinfunction "RXD0_36") (pintype "bidirectional"))
      (node (ref "U1") (pin "40") (pinfunction "PA9_40") (pintype "bidirectional"))
    )
    (net (code "38") (name "Net-(D4-PadC)") (class "Default")
      (node (ref "D4") (pin "C") (pinfunction "C_C") (pintype "passive"))
      (node (ref "R12") (pin "2") (pinfunction "2_2") (pintype "passive"))
    )
    (net (code "39") (name "Net-(IC1-IO19)") (class "Default")
      (node (ref "IC1") (pin "13") (pinfunction "IO19_13") (pintype "bidirectional"))
      (node (ref "R33") (pin "1") (pinfunction "1_1") (pintype "passive"))
    )
    (net (code "40") (name "Net-(IC1-IO20)") (class "Default")
      (node (ref "IC1") (pin "14") (pinfunction "IO20_14") (pintype "bidirectional"))
      (node (ref "R34") (pin "1") (pinfunction "1_1") (pintype "passive"))
    )
    (net (code "41") (name "Net-(IC3-PROG)") (class "Default")
      (node (ref "IC3") (pin "5") (pinfunction "PROG_5") (pintype "input"))
      (node (ref "R11") (pin "2") (pinfunction "2_2") (pintype "passive"))
    )
    (net (code "42") (name "Net-(IC3-STAT)") (class "Default")
      (node (ref "IC3") (pin "1") (pinfunction "STAT_1") (pintype "open_collector"))
      (node (ref "R12") (pin "1") (pinfunction "1_1") (pintype "passive"))
    )
    (net (code "43") (name "Net-(IC5-VIN)") (class "Default")
      (node (ref "C21") (pin "2") (pinfunction "2_2") (pintype "passive"))
      (node (ref "C22") (pin "2") (pinfunction "2_2") (pintype "passive"))
      (node (ref "C24") (pin "2") (pinfunction "2_2") (pintype "passive"))
      (node (ref "IC5") (pin "3") (pinfunction "VIN_3") (pintype "power_in"))
      (node (ref "IC6") (pin "3") (pinfunction "VIN_3") (pintype "power_in"))
      (node (ref "SW4") (pin "5") (pinfunction "C2_5") (pintype "passive"))
    )
    (net (code "44") (name "Net-(IC7-C+)") (class "Default")
      (node (ref "C26") (pin "2") (pinfunction "2_2") (pintype "passive"))
      (node (ref "IC7") (pin "6") (pinfunction "C+_6") (pintype "passive"))
    )
    (net (code "45") (name "Net-(IC7-C-)") (class "Default")
      (node (ref "C26") (pin "1") (pinfunction "1_1") (pintype "passive"))
      (node (ref "IC7") (pin "4") (pinfunction "C-_4") (pintype "passive"))
    )
    (net (code "46") (name "Net-(IC9-BOLX-PadA4)") (class "Default")
      (node (ref "IC9") (pin "A4") (pinfunction "BOLX_A4") (pintype "output"))
      (node (ref "IC9") (pin "B4") (pinfunction "BOLX_B4") (pintype "output"))
      (node (ref "IC9") (pin "C4") (pinfunction "BOLX_C4") (pintype "output"))
      (node (ref "L2") (pin "1") (pinfunction "1_1") (pintype "passive"))
    )
    (net (code "47") (name "Net-(IC9-BULX-PadA2)") (class "Default")
      (node (ref "IC9") (pin "A2") (pinfunction "BULX_A2") (pintype "output"))
      (node (ref "IC9") (pin "B2") (pinfunction "BULX_B2") (pintype "output"))
      (node (ref "IC9") (pin "C2") (pinfunction "BULX_C2") (pintype "output"))
      (node (ref "L2") (pin "2") (pinfunction "2_2") (pintype "passive"))
    )
    (net (code "48") (name "Net-(IC9-CE)") (class "Default")
      (node (ref "IC9") (pin "D2") (pinfunction "CE_D2") (pintype "input"))
      (node (ref "R1") (pin "1") (pinfunction "1_1") (pintype "passive"))
    )
    (net (code "49") (name "Net-(J1-CC1)") (class "Default")
      (node (ref "J1") (pin "A5") (pinfunction "CC1_A5") (pintype "bidirectional"))
      (node (ref "R30") (pin "2") (pinfunction "2_2") (pintype "passive"))
    )
    (net (code "50") (name "Net-(J1-CC2)") (class "Default")
      (node (ref "J1") (pin "B5") (pinfunction "CC2_B5") (pintype "bidirectional"))
      (node (ref "R31") (pin "2") (pinfunction "2_2") (pintype "passive"))
    )
    (net (code "51") (name "Net-(J2-GND-Pad1)") (class "Default")
      (node (ref "J2") (pin "1") (pinfunction "GND_1") (pintype "bidirectional"))
      (node (ref "J2") (pin "2") (pinfunction "GND_2") (pintype "bidirectional"))
      (node (ref "R37") (pin "2") (pinfunction "2_2") (pintype "passive"))
    )
    (net (code "52") (name "Net-(J2-SIGNAL)") (class "Default")
      (node (ref "J2") (pin "FEED") (pinfunction "SIGNAL_FEED") (pintype "bidirectional"))
      (node (ref "U1") (pin "23") (pinfunction "ANT_23") (pintype "bidirectional"))
    )
    (net (code "53") (name "Net-(J6-Pad3)") (class "Default")
      (node (ref "J6") (pin "3") (pinfunction "3_3") (pintype "passive"))
      (node (ref "R8") (pin "1") (pinfunction "1_1") (pintype "passive"))
    )
    (net (code "54") (name "Net-(J6-Pad4)") (class "Default")
      (node (ref "J6") (pin "4") (pinfunction "4_4") (pintype "passive"))
      (node (ref "R16") (pin "1") (pinfunction "1_1") (pintype "passive"))
    )
    (net (code "55") (name "Net-(U1-DCDC_SW)") (class "Default")
      (node (ref "L1") (pin "2") (pinfunction "2_2") (pintype "passive"))
      (node (ref "U1") (pin "3") (pinfunction "DCDC_SW_3") (pintype "output"))
    )
    (net (code "56") (name "Net-(U1-MCU_BOOT0)") (class "Default")
      (node (ref "R38") (pin "2") (pinfunction "2_2") (pintype "passive"))
      (node (ref "U1") (pin "26") (pinfunction "MCU_BOOT0_26") (pintype "input"))
    )
    (net (code "57") (name "Net-(U1-VDD_RF)") (class "Default")
      (node (ref "C10") (pin "2") (pinfunction "2_2") (pintype "passive"))
      (node (ref "C11") (pin "2") (pinfunction "2_2") (pintype "passive"))
      (node (ref "L3") (pin "1") (pinfunction "1_1") (pintype "passive"))
      (node (ref "U1") (pin "5") (pinfunction "VDD_RF_5") (pintype "power_in"))
    )
    (net (code "58") (name "Net-(U1-VREG)") (class "Default")
      (node (ref "L1") (pin "1") (pinfunction "1_1") (pintype "passive"))
      (node (ref "U1") (pin "2") (pinfunction "VREG_2") (pintype "output"))
    )
    (net (code "59") (name "SCL") (class "Default")
      (node (ref "IC1") (pin "39") (pinfunction "IO1_39") (pintype "bidirectional"))
      (node (ref "IC8") (pin "7") (pinfunction "SCL_7") (pintype "bidirectional"))
      (node (ref "J4") (pin "4") (pinfunction "4_4") (pintype "passive"))
      (node (ref "R10") (pin "2") (pinfunction "2_2") (pintype "passive"))
    )
    (net (code "60") (name "SDA") (class "Default")
      (node (ref "IC1") (pin "38") (pinfunction "IO2_38") (pintype "bidirectional"))
      (node (ref "IC8") (pin "8") (pinfunction "SDA_8") (pintype "bidirectional"))
      (node (ref "J4") (pin "3") (pinfunction "3_3") (pintype "passive"))
      (node (ref "R9") (pin "2") (pinfunction "2_2") (pintype "passive"))
    )
    (net (code "61") (name "SDIO_3V3") (class "Default")
      (node (ref "C6") (pin "2") (pinfunction "2_2") (pintype "passive"))
      (node (ref "C7") (pin "2") (pinfunction "2_2") (pintype "passive"))
      (node (ref "Q2") (pin "3") (pinfunction "D_3") (pintype "passive"))
      (node (ref "R26") (pin "2") (pinfunction "2_2") (pintype "passive"))
      (node (ref "R27") (pin "2") (pinfunction "2_2") (pintype "passive"))
      (node (ref "R28") (pin "2") (pinfunction "2_2") (pintype "passive"))
      (node (ref "R29") (pin "2") (pinfunction "2_2") (pintype "passive"))
      (node (ref "SD1") (pin "VCC") (pinfunction "3V3_VCC") (pintype "bidirectional"))
    )
    (net (code "62") (name "SD_CLK") (class "Default")
      (node (ref "IC1") (pin "32") (pinfunction "IO39_32") (pintype "bidirectional"))
      (node (ref "R28") (pin "1") (pinfunction "1_1") (pintype "passive"))
      (node (ref "SD1") (pin "SCK") (pinfunction "SCK_SCK") (pintype "bidirectional"))
    )
    (net (code "63") (name "SD_CMD") (class "Default")
      (node (ref "IC1") (pin "31") (pinfunction "IO38_31") (pintype "bidirectional"))
      (node (ref "R26") (pin "1") (pinfunction "1_1") (pintype "passive"))
      (node (ref "SD1") (pin "MOSI") (pinfunction "MOSI/CMD_MOSI") (pintype "bidirectional"))
    )
    (net (code "64") (name "SD_DAT") (class "Default")
      (node (ref "IC1") (pin "33") (pinfunction "IO40_33") (pintype "bidirectional"))
      (node (ref "R27") (pin "1") (pinfunction "1_1") (pintype "passive"))
      (node (ref "SD1") (pin "MISO") (pinfunction "MISO/DAT0_MISO") (pintype "bidirectional"))
    )
    (net (code "65") (name "SD_ENABLE") (class "Default")
      (node (ref "IC1") (pin "15") (pinfunction "IO3_15") (pintype "bidirectional"))
      (node (ref "Q2") (pin "1") (pinfunction "G_1") (pintype "passive"))
    )
    (net (code "66") (name "SD_SW") (class "Default")
      (node (ref "IC1") (pin "35") (pinfunction "IO42_35") (pintype "bidirectional"))
      (node (ref "R6") (pin "1") (pinfunction "1_1") (pintype "passive"))
      (node (ref "SD1") (pin "SW1") (pinfunction "SW1_SW1") (pintype "bidirectional"))
    )
    (net (code "67") (name "SD_~{CS}") (class "Default")
      (node (ref "IC1") (pin "34") (pinfunction "IO41_34") (pintype "bidirectional"))
      (node (ref "R29") (pin "1") (pinfunction "1_1") (pintype "passive"))
      (node (ref "SD1") (pin "CS") (pinfunction "~{CS}/DAT3_CS") (pintype "bidirectional"))
    )
    (net (code "68") (name "USB-DN") (class "Default")
      (node (ref "D3") (pin "1") (pinfunction "C1_1") (pintype "passive"))
      (node (ref "J1") (pin "A7") (pinfunction "D-_A7") (pintype "bidirectional"))
      (node (ref "J1") (pin "B7") (pinfunction "D-_B7") (pintype "bidirectional"))
      (node (ref "R33") (pin "2") (pinfunction "2_2") (pintype "passive"))
    )
    (net (code "69") (name "USB-DP") (class "Default")
      (node (ref "D3") (pin "2") (pinfunction "C2_2") (pintype "passive"))
      (node (ref "J1") (pin "A6") (pinfunction "D+_A6") (pintype "bidirectional"))
      (node (ref "J1") (pin "B6") (pinfunction "D+_B6") (pintype "bidirectional"))
      (node (ref "R34") (pin "2") (pinfunction "2_2") (pintype "passive"))
    )
    (net (code "70") (name "VBAT") (class "Default")
      (node (ref "C16") (pin "2") (pinfunction "2_2") (pintype "passive"))
      (node (ref "C17") (pin "2") (pinfunction "2_2") (pintype "passive"))
      (node (ref "D2") (pin "6") (pinfunction "VIN2_6") (pintype "power_in"))
      (node (ref "IC3") (pin "3") (pinfunction "VBAT_3") (pintype "bidirectional"))
      (node (ref "IC8") (pin "2") (pinfunction "CELL_2") (pintype "bidirectional"))
      (node (ref "IC8") (pin "3") (pinfunction "VCC_3") (pintype "bidirectional"))
      (node (ref "J3") (pin "1") (pinfunction "1_1") (pintype "passive"))
    )
    (net (code "71") (name "VSWITCHED") (class "Default")
      (node (ref "C25") (pin "2") (pinfunction "2_2") (pintype "passive"))
      (node (ref "C32") (pin "1") (pinfunction "1_1") (pintype "passive"))
      (node (ref "C33") (pin "1") (pinfunction "1_1") (pintype "passive"))
      (node (ref "D2") (pin "2") (pinfunction "VOUT_2") (pintype "power_in"))
      (node (ref "D2") (pin "7") (pinfunction "VOUT_7") (pintype "power_in"))
      (node (ref "IC7") (pin "5") (pinfunction "VIN_5") (pintype "power_in"))
      (node (ref "IC9") (pin "A1") (pinfunction "PVIN_A1") (pintype "power_in"))
      (node (ref "IC9") (pin "B1") (pinfunction "PVIN_B1") (pintype "power_in"))
      (node (ref "IC9") (pin "C1") (pinfunction "PVIN_C1") (pintype "power_in"))
      (node (ref "IC9") (pin "D1") (pinfunction "AVIN_D1") (pintype "power_in"))
      (node (ref "IC9") (pin "D3") (pinfunction "MODE_D3") (pintype "input"))
      (node (ref "SW4") (pin "3") (pinfunction "NC1_3") (pintype "passive"))
      (node (ref "SW4") (pin "6") (pinfunction "NC2_6") (pintype "passive"))
    )
    (net (code "72") (name "VUSB") (class "Default")
      (node (ref "C23") (pin "2") (pinfunction "2_2") (pintype "passive"))
      (node (ref "C28") (pin "2") (pinfunction "2_2") (pintype "passive"))
      (node (ref "D2") (pin "3") (pinfunction "VIN1_3") (pintype "power_in"))
      (node (ref "D4") (pin "A") (pinfunction "A_A") (pintype "passive"))
      (node (ref "IC3") (pin "4") (pinfunction "VIN_4") (pintype "power_in"))
      (node (ref "J1") (pin "VBUS") (pinfunction "VBUS_VBUS") (pintype "power_in"))
      (node (ref "J1") (pin "VBUS2") (pinfunction "VBUS_VBUS2") (pintype "power_in"))
    )
    (net (code "73") (name "V_LED") (class "Default")
      (node (ref "C18") (pin "2") (pinfunction "2_2") (pintype "passive"))
      (node (ref "D1") (pin "4") (pinfunction "VCC_4") (pintype "power_in"))
      (node (ref "R1") (pin "2") (pinfunction "2_2") (pintype "passive"))
      (node (ref "SW4") (pin "2") (pinfunction "C1_2") (pintype "passive"))
    )
    (net (code "74") (name "unconnected-(D1-DO-Pad1)") (class "Default")
      (node (ref "D1") (pin "1") (pinfunction "DO_1") (pintype "bidirectional"))
    )
    (net (code "75") (name "unconnected-(D2-ST-Pad8)") (class "Default")
      (node (ref "D2") (pin "8") (pinfunction "ST_8") (pintype "open_collector"))
    )
    (net (code "76") (name "unconnected-(IC1-IO35-Pad28)") (class "Default")
      (node (ref "IC1") (pin "28") (pinfunction "IO35_28") (pintype "bidirectional"))
    )
    (net (code "77") (name "unconnected-(IC1-IO36-Pad29)") (class "Default")
      (node (ref "IC1") (pin "29") (pinfunction "IO36_29") (pintype "bidirectional"))
    )
    (net (code "78") (name "unconnected-(IC1-IO37-Pad30)") (class "Default")
      (node (ref "IC1") (pin "30") (pinfunction "IO37_30") (pintype "bidirectional"))
    )
    (net (code "79") (name "unconnected-(IC2-NC1-Pad1)") (class "Default")
      (node (ref "IC2") (pin "1") (pinfunction "NC1_1") (pintype "bidirectional"))
    )
    (net (code "80") (name "unconnected-(IC2-Y0-Pad24)") (class "Default")
      (node (ref "IC2") (pin "24") (pinfunction "Y0_24") (pintype "bidirectional"))
    )
    (net (code "81") (name "unconnected-(IC2-Y1-Pad23)") (class "Default")
      (node (ref "IC2") (pin "23") (pinfunction "Y1_23") (pintype "bidirectional"))
    )
    (net (code "82") (name "unconnected-(IC8-~{ALERT}-Pad5)") (class "Default")
      (node (ref "IC8") (pin "5") (pinfunction "~{ALERT}_5") (pintype "bidirectional"))
    )
    (net (code "83") (name "unconnected-(SD1-PadDAT1)") (class "Default")
      (node (ref "SD1") (pin "DAT1") (pinfunction "DAT1_DAT1") (pintype "bidirectional"))
    )
    (net (code "84") (name "unconnected-(SD1-PadDAT2)") (class "Default")
      (node (ref "SD1") (pin "DAT2") (pinfunction "DAT2_DAT2") (pintype "bidirectional"))
    )
    (net (code "85") (name "unconnected-(SW4-NO2-Pad4)") (class "Default")
      (node (ref "SW4") (pin "4") (pinfunction "NO2_4") (pintype "passive"))
    )
    (net (code "86") (name "unconnected-(U1-PA0-Pad17)") (class "Default")
      (node (ref "U1") (pin "17") (pinfunction "PA0_17") (pintype "bidirectional"))
    )
    (net (code "87") (name "unconnected-(U1-PA1-Pad18)") (class "Default")
      (node (ref "U1") (pin "18") (pinfunction "PA1_18") (pintype "bidirectional"))
    )
    (net (code "88") (name "unconnected-(U1-PA2-Pad16)") (class "Default")
      (node (ref "U1") (pin "16") (pinfunction "PA2_16") (pintype "bidirectional"))
    )
    (net (code "89") (name "unconnected-(U1-PA3-Pad15)") (class "Default")
      (node (ref "U1") (pin "15") (pinfunction "PA3_15") (pintype "bidirectional"))
    )
    (net (code "90") (name "unconnected-(U1-PA4-Pad13)") (class "Default")
      (node (ref "U1") (pin "13") (pinfunction "PA4_13") (pintype "bidirectional"))
    )
    (net (code "91") (name "unconnected-(U1-PA5-Pad14)") (class "Default")
      (node (ref "U1") (pin "14") (pinfunction "PA5_14") (pintype "bidirectional"))
    )
    (net (code "92") (name "unconnected-(U1-PA6-Pad11)") (class "Default")
      (node (ref "U1") (pin "11") (pinfunction "PA6_11") (pintype "bidirectional"))
    )
    (net (code "93") (name "unconnected-(U1-PA7-Pad10)") (class "Default")
      (node (ref "U1") (pin "10") (pinfunction "PA7_10") (pintype "bidirectional"))
    )
    (net (code "94") (name "unconnected-(U1-PA8-Pad41)") (class "Default")
      (node (ref "U1") (pin "41") (pinfunction "PA8_41") (pintype "bidirectional"))
    )
    (net (code "95") (name "unconnected-(U1-PA13-Pad33)") (class "Default")
      (node (ref "U1") (pin "33") (pinfunction "PA13_33") (pintype "bidirectional"))
    )
    (net (code "96") (name "unconnected-(U1-PA14-Pad32)") (class "Default")
      (node (ref "U1") (pin "32") (pinfunction "PA14_32") (pintype "bidirectional"))
    )
    (net (code "97") (name "unconnected-(U1-PB2-Pad9)") (class "Default")
      (node (ref "U1") (pin "9") (pinfunction "PB2_9") (pintype "bidirectional"))
    )
    (net (code "98") (name "unconnected-(U1-PB3-Pad28)") (class "Default")
      (node (ref "U1") (pin "28") (pinfunction "PB3_28") (pintype "bidirectional"))
    )
    (net (code "99") (name "unconnected-(U1-PB4-Pad29)") (class "Default")
      (node (ref "U1") (pin "29") (pinfunction "PB4_29") (pintype "bidirectional"))
    )
    (net (code "100") (name "unconnected-(U1-PB5-Pad27)") (class "Default")
      (node (ref "U1") (pin "27") (pinfunction "PB5_27") (pintype "bidirectional"))
    )
    (net (code "101") (name "unconnected-(U1-PB6-Pad30)") (class "Default")
      (node (ref "U1") (pin "30") (pinfunction "PB6_30") (pintype "bidirectional"))
    )
    (net (code "102") (name "unconnected-(U1-PB7-Pad31)") (class "Default")
      (node (ref "U1") (pin "31") (pinfunction "PB7_31") (pintype "bidirectional"))
    )
    (net (code "103") (name "unconnected-(U1-PB8-Pad21)") (class "Default")
      (node (ref "U1") (pin "21") (pinfunction "PB8_21") (pintype "bidirectional"))
    )
    (net (code "104") (name "unconnected-(U1-PB9-Pad20)") (class "Default")
      (node (ref "U1") (pin "20") (pinfunction "PB9_20") (pintype "bidirectional"))
    )
    (net (code "105") (name "unconnected-(U1-PB10-Pad42)") (class "Default")
      (node (ref "U1") (pin "42") (pinfunction "PB10_42") (pintype "bidirectional"))
    )
    (net (code "106") (name "unconnected-(U1-PB11-Pad43)") (class "Default")
      (node (ref "U1") (pin "43") (pinfunction "PB11_43") (pintype "bidirectional"))
    )
  )
)
